# PE.net
KiCad netlist of a schematic drawn in Altium Designer
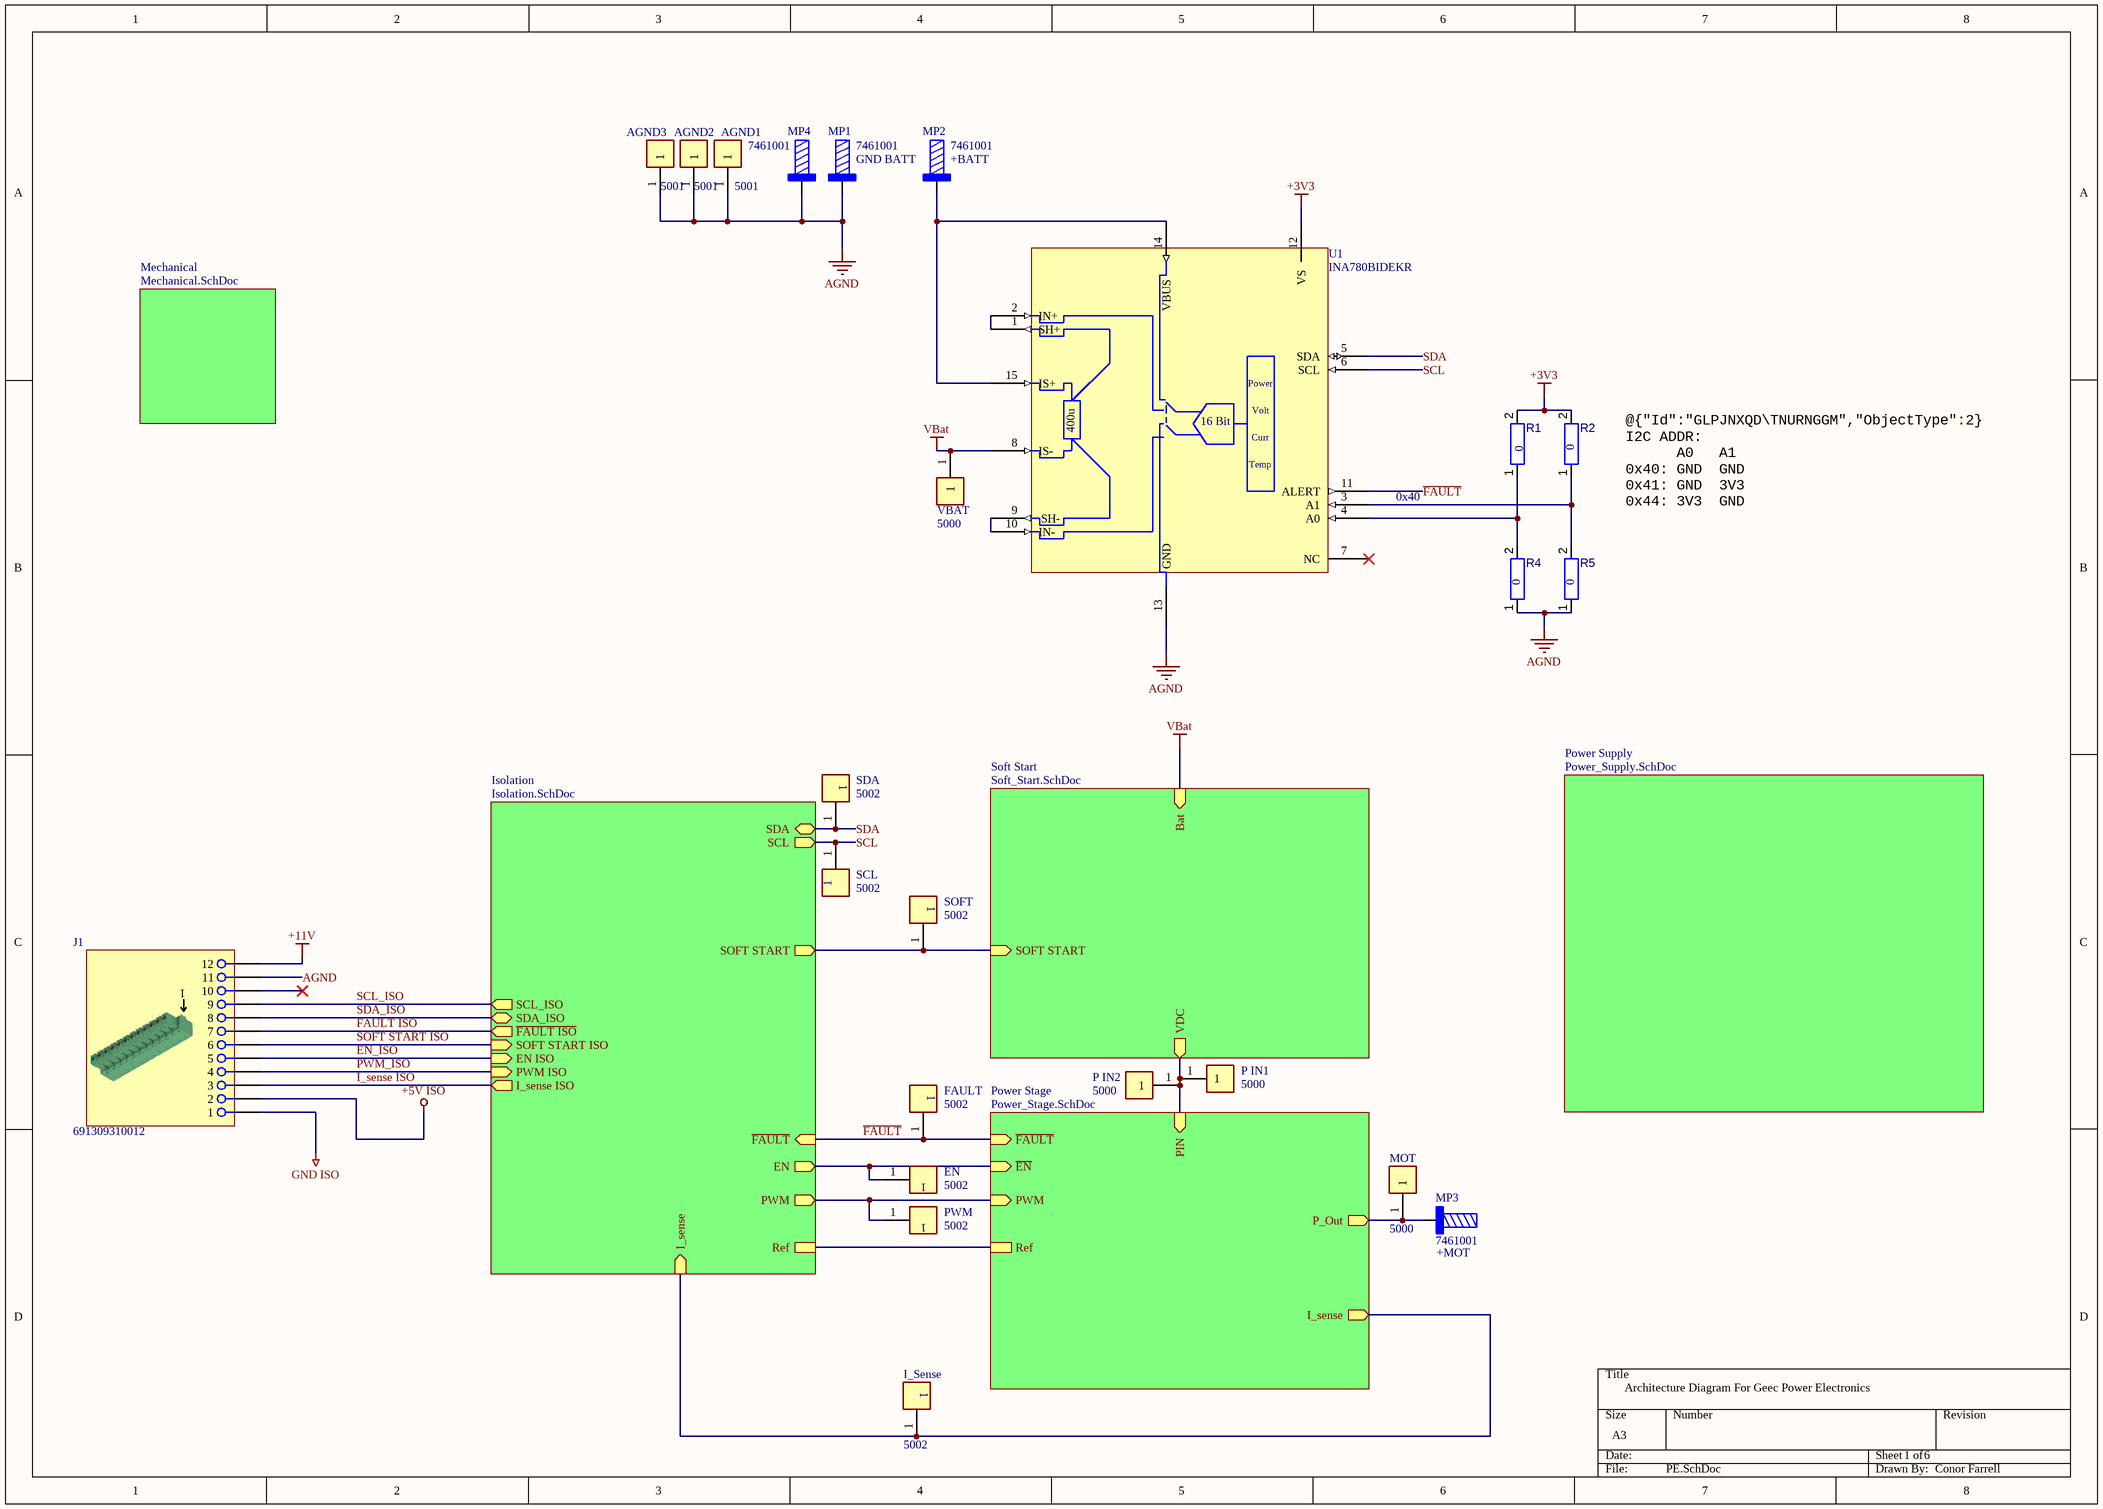
[diagram p0: PE.SchDoc]

(export (version "E")
  (design (tool "Eeschema 10.0.6"))
  (components
    (comp (ref "AGND1")
      (value "5001")
      (footprint "FP-5001-MFG")
      (description "Test Point, Mini, Thm, Pc, .300 L, .100 Od, Heat Resistant Nylon 46, Black")
      (libsource (lib "") (part "1e4615820a309e3ce90f9e6d957b7fa_2"))
    )
    (comp (ref "AGND2")
      (value "5001")
      (footprint "FP-5001-MFG")
      (description "Test Point, Mini, Thm, Pc, .300 L, .100 Od, Heat Resistant Nylon 46, Black")
      (libsource (lib "") (part "1e4615820a309e3ce90f9e6d957b7fa_2"))
    )
    (comp (ref "AGND3")
      (value "5001")
      (footprint "FP-5001-MFG")
      (description "Test Point, Mini, Thm, Pc, .300 L, .100 Od, Heat Resistant Nylon 46, Black")
      (libsource (lib "") (part "1e4615820a309e3ce90f9e6d957b7fa_2"))
    )
    (comp (ref "EN")
      (value "5002")
      (footprint "FP-5002-MFG")
      (description "Test Point, Mini, Thm, Pc, .300 L, .100 Od, Heat Resistant Nylon 46, White")
      (libsource (lib "") (part "1e4615820a309e3ce90f9e6d957b7fa_3"))
    )
    (comp (ref "FAULT")
      (value "5002")
      (footprint "FP-5002-MFG")
      (description "Test Point, Mini, Thm, Pc, .300 L, .100 Od, Heat Resistant Nylon 46, White")
      (libsource (lib "University of Galway") (part "1e4615820a309e3ce90f9e6d957b7fa"))
    )
    (comp (ref "I_Sense")
      (value "5002")
      (footprint "FP-5002-MFG")
      (description "Test Point, Mini, Thm, Pc, .300 L, .100 Od, Heat Resistant Nylon 46, White")
      (libsource (lib "University of Galway") (part "1e4615820a309e3ce90f9e6d957b7fa"))
    )
    (comp (ref "J1")
      (value "691309310012")
      (footprint "691309310012")
      (description "Terminal Block, 3.81MM Pitch, Horizontal With Coding Finger, Tht, 12 Pins")
      (libsource (lib "University of Galway") (part "TBL - 1R - 12P - Female"))
    )
    (comp (ref "MOT")
      (value "5000")
      (footprint "FP-5000-MFG")
      (description "Cable Wrap, 1/2 Inch, Polyethylene, Natural, 50 Ft, Spirap Series")
      (libsource (lib "") (part "1e4615820a309e3ce90f9e6d957b7fa_2"))
    )
    (comp (ref "MP1")
      (value "7461001")
      (footprint "7461001_chemical surface")
      (description "Pcb Terminal, Brass, Press-Fit Rohs Compliant: Yes")
      (libsource (lib "University of Galway") (part "WP-SHFU"))
    )
    (comp (ref "MP2")
      (value "7461001")
      (footprint "7461001_chemical surface")
      (description "Pcb Terminal, Brass, Press-Fit Rohs Compliant: Yes")
      (libsource (lib "University of Galway") (part "WP-SHFU"))
    )
    (comp (ref "MP3")
      (value "7461001")
      (footprint "7461001_chemical surface")
      (description "Pcb Terminal, Brass, Press-Fit Rohs Compliant: Yes")
      (libsource (lib "University of Galway") (part "WP-SHFU"))
    )
    (comp (ref "MP4")
      (value "7461001")
      (footprint "7461001_chemical surface")
      (description "Pcb Terminal, Brass, Press-Fit Rohs Compliant: Yes")
      (libsource (lib "University of Galway") (part "WP-SHFU"))
    )
    (comp (ref "P IN1")
      (value "5000")
      (footprint "FP-5000-MFG")
      (description "Cable Wrap, 1/2 Inch, Polyethylene, Natural, 50 Ft, Spirap Series")
      (libsource (lib "") (part "1e4615820a309e3ce90f9e6d957b7fa_6"))
    )
    (comp (ref "P IN2")
      (value "5000")
      (footprint "FP-5000-MFG")
      (description "Cable Wrap, 1/2 Inch, Polyethylene, Natural, 50 Ft, Spirap Series")
      (libsource (lib "") (part "1e4615820a309e3ce90f9e6d957b7fa_1"))
    )
    (comp (ref "PWM")
      (value "5002")
      (footprint "FP-5002-MFG")
      (description "Test Point, Mini, Thm, Pc, .300 L, .100 Od, Heat Resistant Nylon 46, White")
      (libsource (lib "") (part "1e4615820a309e3ce90f9e6d957b7fa_3"))
    )
    (comp (ref "R1")
      (value "0")
      (footprint "RESC3216X60X45NL15T20")
      (description "Thick Film Resistors - SMD RMC 1206 1/4W 1% T/R-5000")
      (fields (field (name "Comment") "1206W4F0000T5E"))
      (libsource (lib "University of Galway") (part "RES-2"))
    )
    (comp (ref "R2")
      (value "0")
      (footprint "RESC3216X60X45NL15T20")
      (description "Thick Film Resistors - SMD RMC 1206 1/4W 1% T/R-5000")
      (fields (field (name "Comment") "1206W4F0000T5E"))
      (libsource (lib "University of Galway") (part "RES-2"))
    )
    (comp (ref "R4")
      (value "0")
      (footprint "RESC3216X60X45NL15T20")
      (description "Thick Film Resistors - SMD RMC 1206 1/4W 1% T/R-5000")
      (fields (field (name "Comment") "1206W4F0000T5E"))
      (libsource (lib "University of Galway") (part "RES-2"))
    )
    (comp (ref "R5")
      (value "0")
      (footprint "RESC3216X60X45NL15T20")
      (description "Thick Film Resistors - SMD RMC 1206 1/4W 1% T/R-5000")
      (fields (field (name "Comment") "1206W4F0000T5E"))
      (libsource (lib "University of Galway") (part "RES-2"))
    )
    (comp (ref "SCL")
      (value "5002")
      (footprint "FP-5002-MFG")
      (description "Test Point, Mini, Thm, Pc, .300 L, .100 Od, Heat Resistant Nylon 46, White")
      (libsource (lib "") (part "1e4615820a309e3ce90f9e6d957b7fa_4"))
    )
    (comp (ref "SDA")
      (value "5002")
      (footprint "FP-5002-MFG")
      (description "Test Point, Mini, Thm, Pc, .300 L, .100 Od, Heat Resistant Nylon 46, White")
      (libsource (lib "University of Galway") (part "1e4615820a309e3ce90f9e6d957b7fa"))
    )
    (comp (ref "SOFT")
      (value "5002")
      (footprint "FP-5002-MFG")
      (description "Test Point, Mini, Thm, Pc, .300 L, .100 Od, Heat Resistant Nylon 46, White")
      (libsource (lib "University of Galway") (part "1e4615820a309e3ce90f9e6d957b7fa"))
    )
    (comp (ref "U1")
      (value "INA780BIDEKR")
      (footprint "VQFN15_DEK_TEX")
      (description "85-V 16-bit I睠-output digital power monitor with 400-碌Ohm EZShunt Technology 15-VQFN -40 to 125")
      (fields
        (field (name "MANUFACTURER_PART_NUMBER") "PINA780BIDEKR")
        (field (name "COPYRIGHT") "Copyright (C) 2025 Ultra Librarian. All rights reserved.")
      )
      (libsource (lib "University of Galway") (part "PINA780BIDEKR"))
    )
    (comp (ref "VBAT")
      (value "5000")
      (footprint "FP-5000-MFG")
      (description "Cable Wrap, 1/2 Inch, Polyethylene, Natural, 50 Ft, Spirap Series")
      (libsource (lib "") (part "1e4615820a309e3ce90f9e6d957b7fa_5"))
    )
  )
  (nets
    (net (code "1") (name "+3V3") (class "Default")
      (node (ref "R1") (pin "2") (pinfunction "2_2") (pintype "passive"))
      (node (ref "R2") (pin "2") (pinfunction "2_2") (pintype "passive"))
      (node (ref "U1") (pin "12") (pinfunction "VS_12") (pintype "power_in"))
    )
    (net (code "2") (name "+5V ISO") (class "Default")
      (node (ref "J1") (pin "2") (pinfunction "2_2") (pintype "passive"))
    )
    (net (code "3") (name "+11V") (class "Default")
      (node (ref "J1") (pin "12") (pinfunction "12_12") (pintype "passive"))
    )
    (net (code "4") (name "/EN") (class "Default")
      (node (ref "EN") (pin "1") (pinfunction "1_1") (pintype "passive"))
    )
    (net (code "5") (name "/EN_ISO") (class "Default")
      (node (ref "J1") (pin "5") (pinfunction "5_5") (pintype "passive"))
    )
    (net (code "6") (name "/I_sense") (class "Default")
      (node (ref "I_Sense") (pin "1") (pinfunction "1_1") (pintype "passive"))
    )
    (net (code "7") (name "/I_sense ISO") (class "Default")
      (node (ref "J1") (pin "3") (pinfunction "3_3") (pintype "passive"))
    )
    (net (code "8") (name "/PWM") (class "Default")
      (node (ref "PWM") (pin "1") (pinfunction "1_1") (pintype "passive"))
    )
    (net (code "9") (name "/PWM_ISO") (class "Default")
      (node (ref "J1") (pin "4") (pinfunction "4_4") (pintype "passive"))
    )
    (net (code "10") (name "/P_Out") (class "Default")
      (node (ref "MOT") (pin "1") (pinfunction "1_1") (pintype "passive"))
      (node (ref "MP3") (pin "1") (pinfunction "1_1") (pintype "passive"))
    )
    (net (code "12") (name "/SCL") (class "Default")
      (node (ref "SCL") (pin "1") (pinfunction "1_1") (pintype "passive"))
      (node (ref "U1") (pin "6") (pinfunction "SCL_6") (pintype "input"))
    )
    (net (code "13") (name "/SCL_ISO") (class "Default")
      (node (ref "J1") (pin "9") (pinfunction "9_9") (pintype "passive"))
    )
    (net (code "14") (name "/SDA") (class "Default")
      (node (ref "SDA") (pin "1") (pinfunction "1_1") (pintype "passive"))
      (node (ref "U1") (pin "5") (pinfunction "SDA_5") (pintype "bidirectional"))
    )
    (net (code "15") (name "/SDA_ISO") (class "Default")
      (node (ref "J1") (pin "8") (pinfunction "8_8") (pintype "passive"))
    )
    (net (code "16") (name "/SOFT START") (class "Default")
      (node (ref "SOFT") (pin "1") (pinfunction "1_1") (pintype "passive"))
    )
    (net (code "17") (name "/SOFT START ISO") (class "Default")
      (node (ref "J1") (pin "6") (pinfunction "6_6") (pintype "passive"))
    )
    (net (code "18") (name "/VDC") (class "Default")
      (node (ref "P IN1") (pin "1") (pinfunction "1_1") (pintype "passive"))
      (node (ref "P IN2") (pin "1") (pinfunction "1_1") (pintype "passive"))
    )
    (net (code "19") (name "/~{FAULT ISO}") (class "Default")
      (node (ref "J1") (pin "7") (pinfunction "7_7") (pintype "passive"))
    )
    (net (code "20") (name "/~{FAULT}") (class "Default")
      (node (ref "FAULT") (pin "1") (pinfunction "1_1") (pintype "passive"))
      (node (ref "U1") (pin "11") (pinfunction "ALERT_11") (pintype "output"))
    )
    (net (code "21") (name "AGND") (class "Default")
      (node (ref "AGND1") (pin "1") (pinfunction "1_1") (pintype "passive"))
      (node (ref "AGND2") (pin "1") (pinfunction "1_1") (pintype "passive"))
      (node (ref "AGND3") (pin "1") (pinfunction "1_1") (pintype "passive"))
      (node (ref "J1") (pin "11") (pinfunction "11_11") (pintype "passive"))
      (node (ref "MP1") (pin "1") (pinfunction "1_1") (pintype "passive"))
      (node (ref "MP4") (pin "1") (pinfunction "1_1") (pintype "passive"))
      (node (ref "R4") (pin "1") (pinfunction "1_1") (pintype "passive"))
      (node (ref "R5") (pin "1") (pinfunction "1_1") (pintype "passive"))
      (node (ref "U1") (pin "13") (pinfunction "GND_13") (pintype "power_in"))
    )
    (net (code "22") (name "GND ISO") (class "Default")
      (node (ref "J1") (pin "1") (pinfunction "1_1") (pintype "passive"))
    )
    (net (code "23") (name "Net-(U1-A0)") (class "Default")
      (node (ref "R1") (pin "1") (pinfunction "1_1") (pintype "passive"))
      (node (ref "R4") (pin "2") (pinfunction "2_2") (pintype "passive"))
      (node (ref "U1") (pin "4") (pinfunction "A0_4") (pintype "input"))
    )
    (net (code "24") (name "Net-(U1-A1)") (class "Default")
      (node (ref "R2") (pin "1") (pinfunction "1_1") (pintype "passive"))
      (node (ref "R5") (pin "2") (pinfunction "2_2") (pintype "passive"))
      (node (ref "U1") (pin "3") (pinfunction "A1_3") (pintype "input"))
    )
    (net (code "25") (name "Net-(U1-IN+)") (class "Default")
      (node (ref "U1") (pin "1") (pinfunction "SH+_1") (pintype "output"))
      (node (ref "U1") (pin "2") (pinfunction "IN+_2") (pintype "input"))
    )
    (net (code "26") (name "Net-(U1-IN-)") (class "Default")
      (node (ref "U1") (pin "10") (pinfunction "IN-_10") (pintype "input"))
      (node (ref "U1") (pin "9") (pinfunction "SH-_9") (pintype "output"))
    )
    (net (code "27") (name "Net-(U1-IS+)") (class "Default")
      (node (ref "MP2") (pin "1") (pinfunction "1_1") (pintype "passive"))
      (node (ref "U1") (pin "14") (pinfunction "VBUS_14") (pintype "input"))
      (node (ref "U1") (pin "15") (pinfunction "IS+_15") (pintype "input"))
    )
    (net (code "28") (name "VBat") (class "Default")
      (node (ref "U1") (pin "8") (pinfunction "IS-_8") (pintype "input"))
      (node (ref "VBAT") (pin "1") (pinfunction "1_1") (pintype "passive"))
    )
    (net (code "29") (name "unconnected-(J1-Pad10)") (class "Default")
      (node (ref "J1") (pin "10") (pinfunction "10_10") (pintype "passive+no_connect"))
    )
    (net (code "30") (name "unconnected-(U1-NC-Pad7)") (class "Default")
      (node (ref "U1") (pin "7") (pinfunction "NC_7") (pintype "passive+no_connect"))
    )
  )
)
